# moon-rover.net
KiCad netlist of a schematic drawn in EAGLE
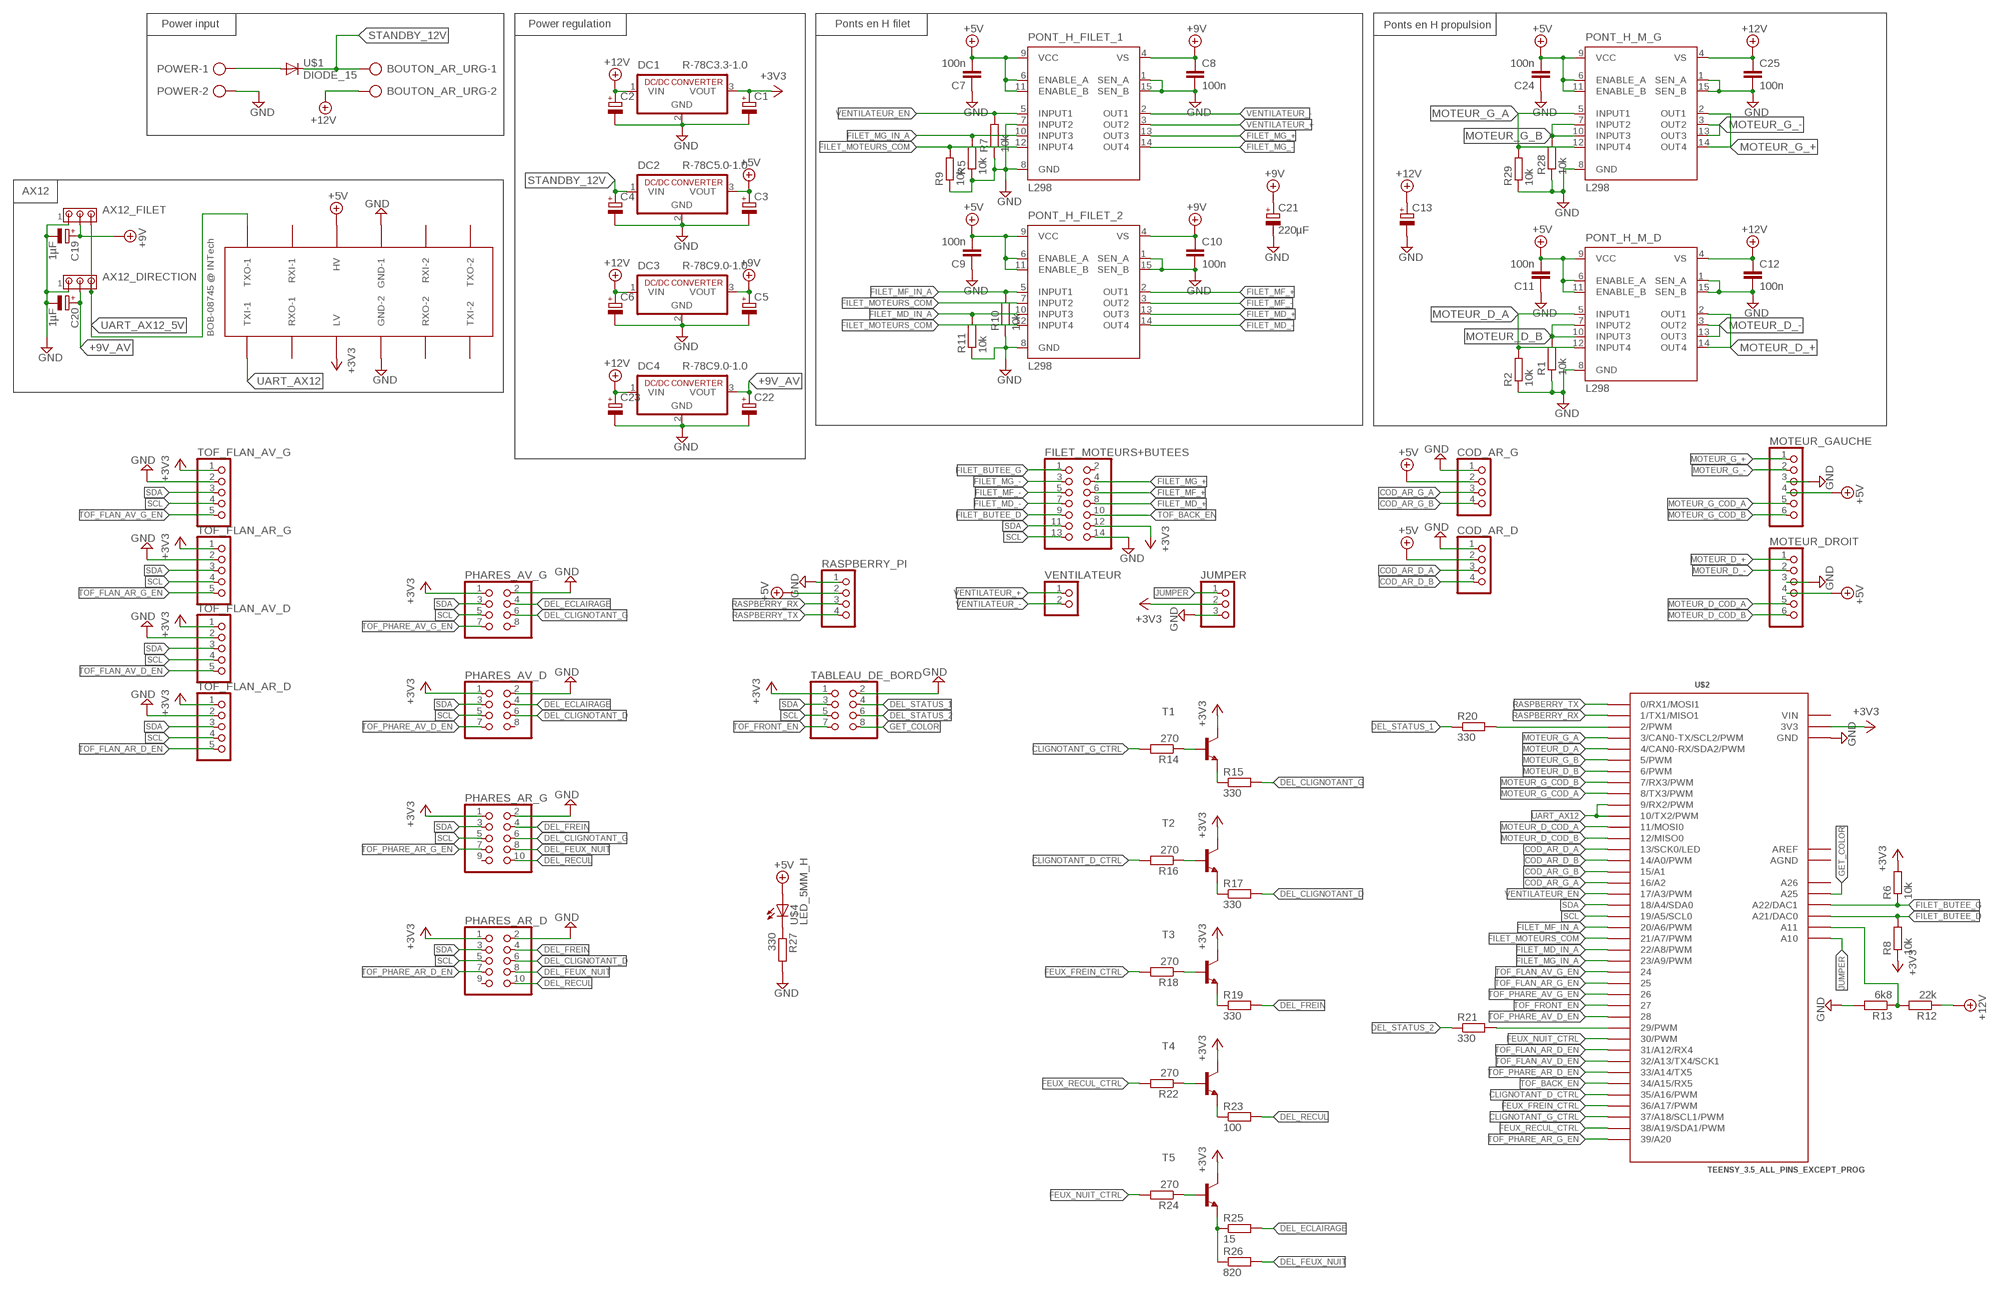
[diagram p0: schematic, sheet 1]

(export (version "E")
  (design (tool "Eeschema 10.0.6"))
  (components
    (comp (ref "AX12_DIRECTION")
      (value "MTA03-100")
      (footprint "eagle-import:10X03MTA")
      (libsource (lib "eagle-import") (part "MTA03-100"))
    )
    (comp (ref "AX12_FILET")
      (value "MTA03-100")
      (footprint "eagle-import:10X03MTA")
      (libsource (lib "eagle-import") (part "MTA03-100"))
    )
    (comp (ref "BOUTON_AR_URG")
      (value "AK300/2")
      (footprint "eagle-import:AK300_2")
      (libsource (lib "eagle-import") (part "AK300/2"))
    )
    (comp (ref "C1")
      (value "CPOL-EUE2.5-6")
      (footprint "eagle-import:E2,5-6")
      (libsource (lib "eagle-import") (part "CPOL-EUE2.5-6"))
    )
    (comp (ref "C2")
      (value "CPOL-EUE2.5-6")
      (footprint "eagle-import:E2,5-6")
      (libsource (lib "eagle-import") (part "CPOL-EUE2.5-6"))
    )
    (comp (ref "C3")
      (value "CPOL-EUE2.5-6")
      (footprint "eagle-import:E2,5-6")
      (libsource (lib "eagle-import") (part "CPOL-EUE2.5-6"))
    )
    (comp (ref "C4")
      (value "CPOL-EUE2.5-6")
      (footprint "eagle-import:E2,5-6")
      (libsource (lib "eagle-import") (part "CPOL-EUE2.5-6"))
    )
    (comp (ref "C5")
      (value "CPOL-EUE2.5-6")
      (footprint "eagle-import:E2,5-6")
      (libsource (lib "eagle-import") (part "CPOL-EUE2.5-6"))
    )
    (comp (ref "C6")
      (value "CPOL-EUE2.5-6")
      (footprint "eagle-import:E2,5-6")
      (libsource (lib "eagle-import") (part "CPOL-EUE2.5-6"))
    )
    (comp (ref "C7")
      (value "100n")
      (footprint "eagle-import:C050-024X044")
      (libsource (lib "eagle-import") (part "C-EU050-024X044"))
    )
    (comp (ref "C8")
      (value "100n")
      (footprint "eagle-import:C050-024X044")
      (libsource (lib "eagle-import") (part "C-EU050-024X044"))
    )
    (comp (ref "C9")
      (value "100n")
      (footprint "eagle-import:C050-024X044")
      (libsource (lib "eagle-import") (part "C-EU050-024X044"))
    )
    (comp (ref "C10")
      (value "100n")
      (footprint "eagle-import:C050-024X044")
      (libsource (lib "eagle-import") (part "C-EU050-024X044"))
    )
    (comp (ref "C11")
      (value "100n")
      (footprint "eagle-import:C050-024X044")
      (libsource (lib "eagle-import") (part "C-EU050-024X044"))
    )
    (comp (ref "C12")
      (value "100n")
      (footprint "eagle-import:C050-024X044")
      (libsource (lib "eagle-import") (part "C-EU050-024X044"))
    )
    (comp (ref "C13")
      (value "CPOL-EUE5-13")
      (footprint "eagle-import:E5-13")
      (libsource (lib "eagle-import") (part "resistor_CPOL-EUE5-13"))
    )
    (comp (ref "C19")
      (value "1µF")
      (footprint "eagle-import:E2,5-5")
      (libsource (lib "eagle-import") (part "CPOL-EUE2.5-5"))
    )
    (comp (ref "C20")
      (value "1µF")
      (footprint "eagle-import:E2,5-5")
      (libsource (lib "eagle-import") (part "CPOL-EUE2.5-5"))
    )
    (comp (ref "C21")
      (value "220µF")
      (footprint "eagle-import:E3,5-8")
      (libsource (lib "eagle-import") (part "CPOL-EUE3.5-8"))
    )
    (comp (ref "C22")
      (value "CPOL-EUE2.5-6")
      (footprint "eagle-import:E2,5-6")
      (libsource (lib "eagle-import") (part "CPOL-EUE2.5-6"))
    )
    (comp (ref "C23")
      (value "CPOL-EUE2.5-6")
      (footprint "eagle-import:E2,5-6")
      (libsource (lib "eagle-import") (part "CPOL-EUE2.5-6"))
    )
    (comp (ref "C24")
      (value "100n")
      (footprint "eagle-import:C050-024X044")
      (libsource (lib "eagle-import") (part "C-EU050-024X044"))
    )
    (comp (ref "C25")
      (value "100n")
      (footprint "eagle-import:C050-024X044")
      (libsource (lib "eagle-import") (part "C-EU050-024X044"))
    )
    (comp (ref "COD_AR_D")
      (value "PINHD-1X4/90")
      (footprint "eagle-import:1X04_90")
      (libsource (lib "eagle-import") (part "PINHD-1X4/90"))
    )
    (comp (ref "COD_AR_G")
      (value "PINHD-1X4/90")
      (footprint "eagle-import:1X04_90")
      (libsource (lib "eagle-import") (part "PINHD-1X4/90"))
    )
    (comp (ref "DC1")
      (value "R-78C3.3-1.0")
      (footprint "eagle-import:SIP3")
      (libsource (lib "eagle-import") (part "R-78C-1.03.3"))
    )
    (comp (ref "DC2")
      (value "R-78C5.0-1.0")
      (footprint "eagle-import:SIP3")
      (libsource (lib "eagle-import") (part "R-78C-1.05.0"))
    )
    (comp (ref "DC3")
      (value "R-78C9.0-1.0")
      (footprint "eagle-import:SIP3")
      (libsource (lib "eagle-import") (part "R-78C-1.09.0"))
    )
    (comp (ref "DC4")
      (value "R-78C9.0-1.0")
      (footprint "eagle-import:SIP3")
      (libsource (lib "eagle-import") (part "R-78C-1.09.0"))
    )
    (comp (ref "FILET_MOTEURS+BUTEES")
      (value "PINHD-2X7")
      (footprint "eagle-import:2X07")
      (libsource (lib "eagle-import") (part "PINHD-2X7"))
    )
    (comp (ref "JUMPER")
      (value "PINHD-1X3/90")
      (footprint "eagle-import:1X03_90")
      (libsource (lib "eagle-import") (part "PINHD-1X3/90"))
    )
    (comp (ref "MOTEUR_DROIT")
      (value "PINHD-1X6/90")
      (footprint "eagle-import:1X06_90")
      (libsource (lib "eagle-import") (part "PINHD-1X6/90"))
    )
    (comp (ref "MOTEUR_GAUCHE")
      (value "PINHD-1X6/90")
      (footprint "eagle-import:1X06_90")
      (libsource (lib "eagle-import") (part "PINHD-1X6/90"))
    )
    (comp (ref "PHARES_AR_D")
      (value "PINHD-2X5")
      (footprint "eagle-import:2X05")
      (libsource (lib "eagle-import") (part "PINHD-2X5"))
    )
    (comp (ref "PHARES_AR_G")
      (value "PINHD-2X5")
      (footprint "eagle-import:2X05")
      (libsource (lib "eagle-import") (part "PINHD-2X5"))
    )
    (comp (ref "PHARES_AV_D")
      (value "PINHD-2X4")
      (footprint "eagle-import:2X04")
      (libsource (lib "eagle-import") (part "PINHD-2X4"))
    )
    (comp (ref "PHARES_AV_G")
      (value "PINHD-2X4")
      (footprint "eagle-import:2X04")
      (libsource (lib "eagle-import") (part "PINHD-2X4"))
    )
    (comp (ref "PONT_H_FILET_1")
      (value "L298")
      (footprint "eagle-import:MULTIWATT-15")
      (fields (field (name "MPN") "L298N"))
      (libsource (lib "eagle-import") (part "L298"))
    )
    (comp (ref "PONT_H_FILET_2")
      (value "L298")
      (footprint "eagle-import:MULTIWATT-15")
      (fields (field (name "MPN") "L298N"))
      (libsource (lib "eagle-import") (part "L298"))
    )
    (comp (ref "PONT_H_M_D")
      (value "L298")
      (footprint "eagle-import:MULTIWATT-15")
      (fields
        (field (name "MPN") "L298N")
        (field (name "MPN_1") "L298N")
        (field (name "OC_FARNELL") "1589425")
        (field (name "OC_NEWARK") "32M1527")
      )
      (libsource (lib "eagle-import") (part "L298"))
    )
    (comp (ref "PONT_H_M_G")
      (value "L298")
      (footprint "eagle-import:MULTIWATT-15")
      (fields
        (field (name "MPN") "L298N")
        (field (name "MPN_1") "L298N")
        (field (name "OC_FARNELL") "1589425")
        (field (name "OC_NEWARK") "32M1527")
      )
      (libsource (lib "eagle-import") (part "L298"))
    )
    (comp (ref "POWER")
      (value "AK300/2")
      (footprint "eagle-import:AK300_2")
      (fields (field (name "OC_FARNELL") "unknown") (field (name "OC_NEWARK") "unknown"))
      (libsource (lib "eagle-import") (part "AK300/2"))
    )
    (comp (ref "R1")
      (value "10k")
      (footprint "eagle-import:0204_7")
      (libsource (lib "eagle-import") (part "R-EU_0204/7"))
    )
    (comp (ref "R2")
      (value "10k")
      (footprint "eagle-import:0204_7")
      (libsource (lib "eagle-import") (part "R-EU_0204/7"))
    )
    (comp (ref "R5")
      (value "10k")
      (footprint "eagle-import:0204_7")
      (libsource (lib "eagle-import") (part "R-EU_0204/7"))
    )
    (comp (ref "R6")
      (value "10k")
      (footprint "eagle-import:0204_7")
      (libsource (lib "eagle-import") (part "R-EU_0204/7"))
    )
    (comp (ref "R7")
      (value "10k")
      (footprint "eagle-import:0204_7")
      (libsource (lib "eagle-import") (part "R-EU_0204/7"))
    )
    (comp (ref "R8")
      (value "10k")
      (footprint "eagle-import:0204_7")
      (libsource (lib "eagle-import") (part "R-EU_0204/7"))
    )
    (comp (ref "R9")
      (value "10k")
      (footprint "eagle-import:0204_7")
      (libsource (lib "eagle-import") (part "R-EU_0204/7"))
    )
    (comp (ref "R10")
      (value "10k")
      (footprint "eagle-import:0204_7")
      (libsource (lib "eagle-import") (part "R-EU_0204/7"))
    )
    (comp (ref "R11")
      (value "10k")
      (footprint "eagle-import:0204_7")
      (libsource (lib "eagle-import") (part "R-EU_0204/7"))
    )
    (comp (ref "R12")
      (value "22k")
      (footprint "eagle-import:0204_7")
      (libsource (lib "eagle-import") (part "R-EU_0204/7"))
    )
    (comp (ref "R13")
      (value "6k8")
      (footprint "eagle-import:0204_7")
      (libsource (lib "eagle-import") (part "R-EU_0204/7"))
    )
    (comp (ref "R14")
      (value "270")
      (footprint "eagle-import:0204_7")
      (libsource (lib "eagle-import") (part "R-EU_0204/7"))
    )
    (comp (ref "R15")
      (value "330")
      (footprint "eagle-import:0207_2V")
      (libsource (lib "eagle-import") (part "R-EU_0207/2V"))
    )
    (comp (ref "R16")
      (value "270")
      (footprint "eagle-import:0204_7")
      (libsource (lib "eagle-import") (part "R-EU_0204/7"))
    )
    (comp (ref "R17")
      (value "330")
      (footprint "eagle-import:0207_2V")
      (libsource (lib "eagle-import") (part "R-EU_0207/2V"))
    )
    (comp (ref "R18")
      (value "270")
      (footprint "eagle-import:0204_7")
      (libsource (lib "eagle-import") (part "R-EU_0204/7"))
    )
    (comp (ref "R19")
      (value "330")
      (footprint "eagle-import:0207_2V")
      (libsource (lib "eagle-import") (part "R-EU_0207/2V"))
    )
    (comp (ref "R20")
      (value "330")
      (footprint "eagle-import:0204_7")
      (libsource (lib "eagle-import") (part "R-EU_0204/7"))
    )
    (comp (ref "R21")
      (value "330")
      (footprint "eagle-import:0207_2V")
      (libsource (lib "eagle-import") (part "R-EU_0207/2V"))
    )
    (comp (ref "R22")
      (value "270")
      (footprint "eagle-import:0204_7")
      (libsource (lib "eagle-import") (part "R-EU_0204/7"))
    )
    (comp (ref "R23")
      (value "100")
      (footprint "eagle-import:0207_2V")
      (libsource (lib "eagle-import") (part "R-EU_0207/2V"))
    )
    (comp (ref "R24")
      (value "270")
      (footprint "eagle-import:0207_2V")
      (libsource (lib "eagle-import") (part "R-EU_0207/2V"))
    )
    (comp (ref "R25")
      (value "15")
      (footprint "eagle-import:0207_2V")
      (libsource (lib "eagle-import") (part "R-EU_0207/2V"))
    )
    (comp (ref "R26")
      (value "820")
      (footprint "eagle-import:0207_2V")
      (libsource (lib "eagle-import") (part "R-EU_0207/2V"))
    )
    (comp (ref "R27")
      (value "330")
      (footprint "eagle-import:0204_7")
      (libsource (lib "eagle-import") (part "R-EU_0204/7"))
    )
    (comp (ref "R28")
      (value "10k")
      (footprint "eagle-import:0204_7")
      (libsource (lib "eagle-import") (part "R-EU_0204/7"))
    )
    (comp (ref "R29")
      (value "10k")
      (footprint "eagle-import:0204_7")
      (libsource (lib "eagle-import") (part "R-EU_0204/7"))
    )
    (comp (ref "RASPBERRY_PI")
      (value "PINHD-1X4/90")
      (footprint "eagle-import:1X04_90")
      (libsource (lib "eagle-import") (part "PINHD-1X4/90"))
    )
    (comp (ref "T1")
      (value "BC237-NPN-TO92-CBE")
      (footprint "eagle-import:TO92-CBE")
      (libsource (lib "eagle-import") (part "-NPN-TO92-CBEBC237"))
    )
    (comp (ref "T2")
      (value "BC237-NPN-TO92-CBE")
      (footprint "eagle-import:TO92-CBE")
      (libsource (lib "eagle-import") (part "-NPN-TO92-CBEBC237"))
    )
    (comp (ref "T3")
      (value "BC237-NPN-TO92-CBE")
      (footprint "eagle-import:TO92-CBE")
      (libsource (lib "eagle-import") (part "-NPN-TO92-CBEBC237"))
    )
    (comp (ref "T4")
      (value "BC237-NPN-TO92-CBE")
      (footprint "eagle-import:TO92-CBE")
      (libsource (lib "eagle-import") (part "-NPN-TO92-CBEBC237"))
    )
    (comp (ref "T5")
      (value "BC237-NPN-TO92-CBE")
      (footprint "eagle-import:TO92-CBE")
      (libsource (lib "eagle-import") (part "-NPN-TO92-CBEBC237"))
    )
    (comp (ref "TABLEAU_DE_BORD")
      (value "PINHD-2X4")
      (footprint "eagle-import:2X04")
      (libsource (lib "eagle-import") (part "PINHD-2X4"))
    )
    (comp (ref "TOF_FLAN_AR_D")
      (value "PINHD-1X5")
      (footprint "eagle-import:1X05")
      (libsource (lib "eagle-import") (part "PINHD-1X5"))
    )
    (comp (ref "TOF_FLAN_AR_G")
      (value "PINHD-1X5")
      (footprint "eagle-import:1X05")
      (libsource (lib "eagle-import") (part "PINHD-1X5"))
    )
    (comp (ref "TOF_FLAN_AV_D")
      (value "PINHD-1X5")
      (footprint "eagle-import:1X05")
      (libsource (lib "eagle-import") (part "PINHD-1X5"))
    )
    (comp (ref "TOF_FLAN_AV_G")
      (value "PINHD-1X5")
      (footprint "eagle-import:1X05")
      (libsource (lib "eagle-import") (part "PINHD-1X5"))
    )
    (comp (ref "U$1")
      (value "DIODE_15")
      (footprint "eagle-import:DO201-15")
      (libsource (lib "eagle-import") (part "DIODE_15"))
    )
    (comp (ref "U$2")
      (value "TEENSY_3.5_ALL_PINS_EXCEPT_PROG")
      (footprint "eagle-import:TEENSY_3.5_ALL_PINS_EXCEPT_PROG")
      (libsource (lib "eagle-import") (part "TEENSY_3.5_ALL_PINS_EXCEPT_PROG"))
    )
    (comp (ref "U$3")
      (value "BOB-08745")
      (footprint "eagle-import:BOB-08745")
      (libsource (lib "eagle-import") (part "BOB-08745"))
    )
    (comp (ref "U$4")
      (value "LED_5MM_H")
      (footprint "eagle-import:Q62902-B155")
      (libsource (lib "eagle-import") (part "LED_5MM_H"))
    )
    (comp (ref "VENTILATEUR")
      (value "PINHD-1X2/90")
      (footprint "eagle-import:1X02_90")
      (libsource (lib "eagle-import") (part "PINHD-1X2/90"))
    )
  )
  (nets
    (net (code "1") (name "+3V3") (class "Default")
      (node (ref "C1") (pin "+") (pinfunction "+_+") (pintype "passive"))
      (node (ref "DC1") (pin "3") (pinfunction "VOUT_3") (pintype "passive"))
      (node (ref "FILET_MOTEURS+BUTEES") (pin "12") (pinfunction "12_12") (pintype "passive"))
      (node (ref "JUMPER") (pin "2") (pinfunction "2_2") (pintype "passive"))
      (node (ref "PHARES_AR_D") (pin "1") (pinfunction "1_1") (pintype "passive"))
      (node (ref "PHARES_AR_G") (pin "1") (pinfunction "1_1") (pintype "passive"))
      (node (ref "PHARES_AV_D") (pin "1") (pinfunction "1_1") (pintype "passive"))
      (node (ref "PHARES_AV_G") (pin "1") (pinfunction "1_1") (pintype "passive"))
      (node (ref "R6") (pin "2") (pinfunction "2_2") (pintype "passive"))
      (node (ref "R8") (pin "1") (pinfunction "1_1") (pintype "passive"))
      (node (ref "T1") (pin "C") (pinfunction "C_C") (pintype "passive"))
      (node (ref "T2") (pin "C") (pinfunction "C_C") (pintype "passive"))
      (node (ref "T3") (pin "C") (pinfunction "C_C") (pintype "passive"))
      (node (ref "T4") (pin "C") (pinfunction "C_C") (pintype "passive"))
      (node (ref "T5") (pin "C") (pinfunction "C_C") (pintype "passive"))
      (node (ref "TABLEAU_DE_BORD") (pin "1") (pinfunction "1_1") (pintype "passive"))
      (node (ref "TOF_FLAN_AR_D") (pin "1") (pinfunction "1_1") (pintype "passive"))
      (node (ref "TOF_FLAN_AR_G") (pin "1") (pinfunction "1_1") (pintype "passive"))
      (node (ref "TOF_FLAN_AV_D") (pin "1") (pinfunction "1_1") (pintype "passive"))
      (node (ref "TOF_FLAN_AV_G") (pin "1") (pinfunction "1_1") (pintype "passive"))
      (node (ref "U$2") (pin "3.3V") (pinfunction "3V3_3.3V") (pintype "power_in"))
      (node (ref "U$2") (pin "3.3V3") (pinfunction "3V3_3.3V3") (pintype "power_in"))
      (node (ref "U$3") (pin "LV") (pinfunction "LV_LV") (pintype "bidirectional"))
    )
    (net (code "2") (name "+5V") (class "Default")
      (node (ref "C11") (pin "2") (pinfunction "2_2") (pintype "passive"))
      (node (ref "C24") (pin "2") (pinfunction "2_2") (pintype "passive"))
      (node (ref "C3") (pin "+") (pinfunction "+_+") (pintype "passive"))
      (node (ref "C7") (pin "2") (pinfunction "2_2") (pintype "passive"))
      (node (ref "C9") (pin "2") (pinfunction "2_2") (pintype "passive"))
      (node (ref "COD_AR_D") (pin "2") (pinfunction "2_2") (pintype "passive"))
      (node (ref "COD_AR_G") (pin "2") (pinfunction "2_2") (pintype "passive"))
      (node (ref "DC2") (pin "3") (pinfunction "VOUT_3") (pintype "passive"))
      (node (ref "MOTEUR_DROIT") (pin "4") (pinfunction "4_4") (pintype "passive"))
      (node (ref "MOTEUR_GAUCHE") (pin "4") (pinfunction "4_4") (pintype "passive"))
      (node (ref "PONT_H_FILET_1") (pin "11") (pinfunction "ENABLE_B_11") (pintype "input"))
      (node (ref "PONT_H_FILET_1") (pin "6") (pinfunction "ENABLE_A_6") (pintype "input"))
      (node (ref "PONT_H_FILET_1") (pin "9") (pinfunction "VCC_9") (pintype "power_in"))
      (node (ref "PONT_H_FILET_2") (pin "11") (pinfunction "ENABLE_B_11") (pintype "input"))
      (node (ref "PONT_H_FILET_2") (pin "6") (pinfunction "ENABLE_A_6") (pintype "input"))
      (node (ref "PONT_H_FILET_2") (pin "9") (pinfunction "VCC_9") (pintype "power_in"))
      (node (ref "PONT_H_M_D") (pin "11") (pinfunction "ENABLE_B_11") (pintype "input"))
      (node (ref "PONT_H_M_D") (pin "6") (pinfunction "ENABLE_A_6") (pintype "input"))
      (node (ref "PONT_H_M_D") (pin "9") (pinfunction "VCC_9") (pintype "power_in"))
      (node (ref "PONT_H_M_G") (pin "11") (pinfunction "ENABLE_B_11") (pintype "input"))
      (node (ref "PONT_H_M_G") (pin "6") (pinfunction "ENABLE_A_6") (pintype "input"))
      (node (ref "PONT_H_M_G") (pin "9") (pinfunction "VCC_9") (pintype "power_in"))
      (node (ref "RASPBERRY_PI") (pin "2") (pinfunction "2_2") (pintype "passive"))
      (node (ref "U$3") (pin "HV") (pinfunction "HV_HV") (pintype "bidirectional"))
      (node (ref "U$4") (pin "A+") (pinfunction "A+_A+") (pintype "passive"))
    )
    (net (code "3") (name "+9V") (class "Default")
      (node (ref "AX12_FILET") (pin "2") (pinfunction "2_2") (pintype "passive"))
      (node (ref "C10") (pin "1") (pinfunction "1_1") (pintype "passive"))
      (node (ref "C19") (pin "+") (pinfunction "+_+") (pintype "passive"))
      (node (ref "C21") (pin "+") (pinfunction "+_+") (pintype "passive"))
      (node (ref "C5") (pin "+") (pinfunction "+_+") (pintype "passive"))
      (node (ref "C8") (pin "1") (pinfunction "1_1") (pintype "passive"))
      (node (ref "DC3") (pin "3") (pinfunction "VOUT_3") (pintype "passive"))
      (node (ref "PONT_H_FILET_1") (pin "4") (pinfunction "VS_4") (pintype "power_in"))
      (node (ref "PONT_H_FILET_2") (pin "4") (pinfunction "VS_4") (pintype "power_in"))
    )
    (net (code "4") (name "+9V_AV") (class "Default")
      (node (ref "AX12_DIRECTION") (pin "2") (pinfunction "2_2") (pintype "passive"))
      (node (ref "C20") (pin "+") (pinfunction "+_+") (pintype "passive"))
      (node (ref "C22") (pin "+") (pinfunction "+_+") (pintype "passive"))
      (node (ref "DC4") (pin "3") (pinfunction "VOUT_3") (pintype "passive"))
    )
    (net (code "5") (name "+12V") (class "Default")
      (node (ref "BOUTON_AR_URG") (pin "2") (pinfunction "KL_2") (pintype "passive"))
      (node (ref "C12") (pin "1") (pinfunction "1_1") (pintype "passive"))
      (node (ref "C13") (pin "+") (pinfunction "+_+") (pintype "passive"))
      (node (ref "C2") (pin "+") (pinfunction "+_+") (pintype "passive"))
      (node (ref "C23") (pin "+") (pinfunction "+_+") (pintype "passive"))
      (node (ref "C25") (pin "1") (pinfunction "1_1") (pintype "passive"))
      (node (ref "C6") (pin "+") (pinfunction "+_+") (pintype "passive"))
      (node (ref "DC1") (pin "1") (pinfunction "VIN_1") (pintype "passive"))
      (node (ref "DC3") (pin "1") (pinfunction "VIN_1") (pintype "passive"))
      (node (ref "DC4") (pin "1") (pinfunction "VIN_1") (pintype "passive"))
      (node (ref "PONT_H_M_D") (pin "4") (pinfunction "VS_4") (pintype "power_in"))
      (node (ref "PONT_H_M_G") (pin "4") (pinfunction "VS_4") (pintype "power_in"))
      (node (ref "R12") (pin "1") (pinfunction "1_1") (pintype "passive"))
    )
    (net (code "6") (name "/AGND") (class "Default")
      (node (ref "U$2") (pin "AGND") (pinfunction "AGND_AGND") (pintype "power_in"))
    )
    (net (code "7") (name "/AREF") (class "Default")
      (node (ref "U$2") (pin "AREF") (pinfunction "AREF_AREF") (pintype "power_in"))
    )
    (net (code "8") (name "/VIN") (class "Default")
      (node (ref "U$2") (pin "VIN") (pinfunction "VIN_VIN") (pintype "power_in"))
    )
    (net (code "9") (name "CLIGNOTANT_D_CTRL") (class "Default")
      (node (ref "R16") (pin "2") (pinfunction "2_2") (pintype "passive"))
      (node (ref "U$2") (pin "35/A16") (pinfunction "35/A16/PWM_35/A16") (pintype "bidirectional"))
    )
    (net (code "10") (name "CLIGNOTANT_G_CTRL") (class "Default")
      (node (ref "R14") (pin "2") (pinfunction "2_2") (pintype "passive"))
      (node (ref "U$2") (pin "37/A18") (pinfunction "37/A18/SCL1/PWM_37/A18") (pintype "bidirectional"))
    )
    (net (code "11") (name "COD_AR_D_A") (class "Default")
      (node (ref "COD_AR_D") (pin "3") (pinfunction "3_3") (pintype "passive"))
      (node (ref "U$2") (pin "13") (pinfunction "13/SCK0/LED_13") (pintype "bidirectional"))
    )
    (net (code "12") (name "COD_AR_D_B") (class "Default")
      (node (ref "COD_AR_D") (pin "4") (pinfunction "4_4") (pintype "passive"))
      (node (ref "U$2") (pin "14/A0") (pinfunction "14/A0/PWM_14/A0") (pintype "bidirectional"))
    )
    (net (code "13") (name "COD_AR_G_A") (class "Default")
      (node (ref "COD_AR_G") (pin "3") (pinfunction "3_3") (pintype "passive"))
      (node (ref "U$2") (pin "16/A2") (pinfunction "16/A2_16/A2") (pintype "bidirectional"))
    )
    (net (code "14") (name "COD_AR_G_B") (class "Default")
      (node (ref "COD_AR_G") (pin "4") (pinfunction "4_4") (pintype "passive"))
      (node (ref "U$2") (pin "15/A1") (pinfunction "15/A1_15/A1") (pintype "bidirectional"))
    )
    (net (code "15") (name "DEL_CLIGNOTANT_D") (class "Default")
      (node (ref "PHARES_AR_D") (pin "6") (pinfunction "6_6") (pintype "passive"))
      (node (ref "PHARES_AV_D") (pin "6") (pinfunction "6_6") (pintype "passive"))
      (node (ref "R17") (pin "2") (pinfunction "2_2") (pintype "passive"))
    )
    (net (code "16") (name "DEL_CLIGNOTANT_G") (class "Default")
      (node (ref "PHARES_AR_G") (pin "6") (pinfunction "6_6") (pintype "passive"))
      (node (ref "PHARES_AV_G") (pin "6") (pinfunction "6_6") (pintype "passive"))
      (node (ref "R15") (pin "2") (pinfunction "2_2") (pintype "passive"))
    )
    (net (code "17") (name "DEL_ECLAIRAGE") (class "Default")
      (node (ref "PHARES_AV_D") (pin "4") (pinfunction "4_4") (pintype "passive"))
      (node (ref "PHARES_AV_G") (pin "4") (pinfunction "4_4") (pintype "passive"))
      (node (ref "R25") (pin "2") (pinfunction "2_2") (pintype "passive"))
    )
    (net (code "18") (name "DEL_FEUX_NUIT") (class "Default")
      (node (ref "PHARES_AR_D") (pin "8") (pinfunction "8_8") (pintype "passive"))
      (node (ref "PHARES_AR_G") (pin "8") (pinfunction "8_8") (pintype "passive"))
      (node (ref "R26") (pin "2") (pinfunction "2_2") (pintype "passive"))
    )
    (net (code "19") (name "DEL_FREIN") (class "Default")
      (node (ref "PHARES_AR_D") (pin "4") (pinfunction "4_4") (pintype "passive"))
      (node (ref "PHARES_AR_G") (pin "4") (pinfunction "4_4") (pintype "passive"))
      (node (ref "R19") (pin "2") (pinfunction "2_2") (pintype "passive"))
    )
    (net (code "20") (name "DEL_RECUL") (class "Default")
      (node (ref "PHARES_AR_D") (pin "10") (pinfunction "10_10") (pintype "passive"))
      (node (ref "PHARES_AR_G") (pin "10") (pinfunction "10_10") (pintype "passive"))
      (node (ref "R23") (pin "2") (pinfunction "2_2") (pintype "passive"))
    )
    (net (code "21") (name "DEL_STATUS_1") (class "Default")
      (node (ref "R20") (pin "1") (pinfunction "1_1") (pintype "passive"))
      (node (ref "TABLEAU_DE_BORD") (pin "4") (pinfunction "4_4") (pintype "passive"))
    )
    (net (code "22") (name "DEL_STATUS_2") (class "Default")
      (node (ref "R21") (pin "1") (pinfunction "1_1") (pintype "passive"))
      (node (ref "TABLEAU_DE_BORD") (pin "6") (pinfunction "6_6") (pintype "passive"))
    )
    (net (code "23") (name "FEUX_FREIN_CTRL") (class "Default")
      (node (ref "R18") (pin "2") (pinfunction "2_2") (pintype "passive"))
      (node (ref "U$2") (pin "36/A17") (pinfunction "36/A17/PWM_36/A17") (pintype "bidirectional"))
    )
    (net (code "24") (name "FEUX_NUIT_CTRL") (class "Default")
      (node (ref "R24") (pin "2") (pinfunction "2_2") (pintype "passive"))
      (node (ref "U$2") (pin "30") (pinfunction "30/PWM_30") (pintype "bidirectional"))
    )
    (net (code "25") (name "FEUX_RECUL_CTRL") (class "Default")
      (node (ref "R22") (pin "2") (pinfunction "2_2") (pintype "passive"))
      (node (ref "U$2") (pin "38/A19") (pinfunction "38/A19/SDA1/PWM_38/A19") (pintype "bidirectional"))
    )
    (net (code "26") (name "FILET_BUTEE_D") (class "Default")
      (node (ref "FILET_MOTEURS+BUTEES") (pin "9") (pinfunction "9_9") (pintype "passive"))
      (node (ref "R8") (pin "2") (pinfunction "2_2") (pintype "passive"))
      (node (ref "U$2") (pin "A21") (pinfunction "A21/DAC0_A21") (pintype "bidirectional"))
    )
    (net (code "27") (name "FILET_BUTEE_G") (class "Default")
      (node (ref "FILET_MOTEURS+BUTEES") (pin "1") (pinfunction "1_1") (pintype "passive"))
      (node (ref "R6") (pin "1") (pinfunction "1_1") (pintype "passive"))
      (node (ref "U$2") (pin "A22") (pinfunction "A22/DAC1_A22") (pintype "bidirectional"))
    )
    (net (code "28") (name "FILET_MD_+") (class "Default")
      (node (ref "FILET_MOTEURS+BUTEES") (pin "8") (pinfunction "8_8") (pintype "passive"))
      (node (ref "PONT_H_FILET_2") (pin "13") (pinfunction "OUT3_13") (pintype "output"))
    )
    (net (code "29") (name "FILET_MD_-") (class "Default")
      (node (ref "FILET_MOTEURS+BUTEES") (pin "7") (pinfunction "7_7") (pintype "passive"))
      (node (ref "PONT_H_FILET_2") (pin "14") (pinfunction "OUT4_14") (pintype "output"))
    )
    (net (code "30") (name "FILET_MD_IN_A") (class "Default")
      (node (ref "PONT_H_FILET_2") (pin "10") (pinfunction "INPUT3_10") (pintype "input"))
      (node (ref "R11") (pin "2") (pinfunction "2_2") (pintype "passive"))
      (node (ref "U$2") (pin "22/A8") (pinfunction "22/A8/PWM_22/A8") (pintype "bidirectional"))
    )
    (net (code "31") (name "FILET_MF_+") (class "Default")
      (node (ref "FILET_MOTEURS+BUTEES") (pin "6") (pinfunction "6_6") (pintype "passive"))
      (node (ref "PONT_H_FILET_2") (pin "2") (pinfunction "OUT1_2") (pintype "output"))
    )
    (net (code "32") (name "FILET_MF_-") (class "Default")
      (node (ref "FILET_MOTEURS+BUTEES") (pin "5") (pinfunction "5_5") (pintype "passive"))
      (node (ref "PONT_H_FILET_2") (pin "3") (pinfunction "OUT2_3") (pintype "output"))
    )
    (net (code "33") (name "FILET_MF_IN_A") (class "Default")
      (node (ref "PONT_H_FILET_2") (pin "5") (pinfunction "INPUT1_5") (pintype "input"))
      (node (ref "R10") (pin "2") (pinfunction "2_2") (pintype "passive"))
      (node (ref "U$2") (pin "20/A6") (pinfunction "20/A6/PWM_20/A6") (pintype "bidirectional"))
    )
    (net (code "34") (name "FILET_MG_+") (class "Default")
      (node (ref "FILET_MOTEURS+BUTEES") (pin "4") (pinfunction "4_4") (pintype "passive"))
      (node (ref "PONT_H_FILET_1") (pin "13") (pinfunction "OUT3_13") (pintype "output"))
    )
    (net (code "35") (name "FILET_MG_-") (class "Default")
      (node (ref "FILET_MOTEURS+BUTEES") (pin "3") (pinfunction "3_3") (pintype "passive"))
      (node (ref "PONT_H_FILET_1") (pin "14") (pinfunction "OUT4_14") (pintype "output"))
    )
    (net (code "36") (name "FILET_MG_IN_A") (class "Default")
      (node (ref "PONT_H_FILET_1") (pin "10") (pinfunction "INPUT3_10") (pintype "input"))
      (node (ref "R5") (pin "2") (pinfunction "2_2") (pintype "passive"))
      (node (ref "U$2") (pin "23/A9") (pinfunction "23/A9/PWM_23/A9") (pintype "bidirectional"))
    )
    (net (code "37") (name "FILET_MOTEURS_COM") (class "Default")
      (node (ref "PONT_H_FILET_1") (pin "12") (pinfunction "INPUT4_12") (pintype "input"))
      (node (ref "PONT_H_FILET_2") (pin "12") (pinfunction "INPUT4_12") (pintype "input"))
      (node (ref "PONT_H_FILET_2") (pin "7") (pinfunction "INPUT2_7") (pintype "input"))
      (node (ref "R9") (pin "2") (pinfunction "2_2") (pintype "passive"))
      (node (ref "U$2") (pin "21/A7") (pinfunction "21/A7/PWM_21/A7") (pintype "bidirectional"))
    )
    (net (code "38") (name "GET_COLOR") (class "Default")
      (node (ref "TABLEAU_DE_BORD") (pin "8") (pinfunction "8_8") (pintype "passive"))
      (node (ref "U$2") (pin "A25") (pinfunction "A25_A25") (pintype "bidirectional"))
    )
    (net (code "39") (name "GND") (class "Default")
      (node (ref "AX12_DIRECTION") (pin "1") (pinfunction "1_1") (pintype "passive"))
      (node (ref "AX12_FILET") (pin "1") (pinfunction "1_1") (pintype "passive"))
      (node (ref "C1") (pin "-") (pinfunction "-_-") (pintype "passive"))
      (node (ref "C10") (pin "2") (pinfunction "2_2") (pintype "passive"))
      (node (ref "C11") (pin "1") (pinfunction "1_1") (pintype "passive"))
      (node (ref "C12") (pin "2") (pinfunction "2_2") (pintype "passive"))
      (node (ref "C13") (pin "-") (pinfunction "-_-") (pintype "passive"))
      (node (ref "C19") (pin "-") (pinfunction "-_-") (pintype "passive"))
      (node (ref "C2") (pin "-") (pinfunction "-_-") (pintype "passive"))
      (node (ref "C20") (pin "-") (pinfunction "-_-") (pintype "passive"))
      (node (ref "C21") (pin "-") (pinfunction "-_-") (pintype "passive"))
      (node (ref "C22") (pin "-") (pinfunction "-_-") (pintype "passive"))
      (node (ref "C23") (pin "-") (pinfunction "-_-") (pintype "passive"))
      (node (ref "C24") (pin "1") (pinfunction "1_1") (pintype "passive"))
      (node (ref "C25") (pin "2") (pinfunction "2_2") (pintype "passive"))
      (node (ref "C3") (pin "-") (pinfunction "-_-") (pintype "passive"))
      (node (ref "C4") (pin "-") (pinfunction "-_-") (pintype "passive"))
      (node (ref "C5") (pin "-") (pinfunction "-_-") (pintype "passive"))
      (node (ref "C6") (pin "-") (pinfunction "-_-") (pintype "passive"))
      (node (ref "C7") (pin "1") (pinfunction "1_1") (pintype "passive"))
      (node (ref "C8") (pin "2") (pinfunction "2_2") (pintype "passive"))
      (node (ref "C9") (pin "1") (pinfunction "1_1") (pintype "passive"))
      (node (ref "COD_AR_D") (pin "1") (pinfunction "1_1") (pintype "passive"))
      (node (ref "COD_AR_G") (pin "1") (pinfunction "1_1") (pintype "passive"))
      (node (ref "DC1") (pin "2") (pinfunction "GND_2") (pintype "passive"))
      (node (ref "DC2") (pin "2") (pinfunction "GND_2") (pintype "passive"))
      (node (ref "DC3") (pin "2") (pinfunction "GND_2") (pintype "passive"))
      (node (ref "DC4") (pin "2") (pinfunction "GND_2") (pintype "passive"))
      (node (ref "FILET_MOTEURS+BUTEES") (pin "14") (pinfunction "14_14") (pintype "passive"))
      (node (ref "JUMPER") (pin "3") (pinfunction "3_3") (pintype "passive"))
      (node (ref "MOTEUR_DROIT") (pin "3") (pinfunction "3_3") (pintype "passive"))
      (node (ref "MOTEUR_GAUCHE") (pin "3") (pinfunction "3_3") (pintype "passive"))
      (node (ref "PHARES_AR_D") (pin "2") (pinfunction "2_2") (pintype "passive"))
      (node (ref "PHARES_AR_G") (pin "2") (pinfunction "2_2") (pintype "passive"))
      (node (ref "PHARES_AV_D") (pin "2") (pinfunction "2_2") (pintype "passive"))
      (node (ref "PHARES_AV_G") (pin "2") (pinfunction "2_2") (pintype "passive"))
      (node (ref "PONT_H_FILET_1") (pin "1") (pinfunction "SEN_A_1") (pintype "input"))
      (node (ref "PONT_H_FILET_1") (pin "15") (pinfunction "SEN_B_15") (pintype "input"))
      (node (ref "PONT_H_FILET_1") (pin "7") (pinfunction "INPUT2_7") (pintype "input"))
      (node (ref "PONT_H_FILET_1") (pin "8") (pinfunction "GND_8") (pintype "power_in"))
      (node (ref "PONT_H_FILET_2") (pin "1") (pinfunction "SEN_A_1") (pintype "input"))
      (node (ref "PONT_H_FILET_2") (pin "15") (pinfunction "SEN_B_15") (pintype "input"))
      (node (ref "PONT_H_FILET_2") (pin "8") (pinfunction "GND_8") (pintype "power_in"))
      (node (ref "PONT_H_M_D") (pin "1") (pinfunction "SEN_A_1") (pintype "input"))
      (node (ref "PONT_H_M_D") (pin "15") (pinfunction "SEN_B_15") (pintype "input"))
      (node (ref "PONT_H_M_D") (pin "8") (pinfunction "GND_8") (pintype "power_in"))
      (node (ref "PONT_H_M_G") (pin "1") (pinfunction "SEN_A_1") (pintype "input"))
      (node (ref "PONT_H_M_G") (pin "15") (pinfunction "SEN_B_15") (pintype "input"))
      (node (ref "PONT_H_M_G") (pin "8") (pinfunction "GND_8") (pintype "power_in"))
      (node (ref "POWER") (pin "2") (pinfunction "KL_2") (pintype "passive"))
      (node (ref "R1") (pin "1") (pinfunction "1_1") (pintype "passive"))
      (node (ref "R10") (pin "1") (pinfunction "1_1") (pintype "passive"))
      (node (ref "R11") (pin "1") (pinfunction "1_1") (pintype "passive"))
      (node (ref "R13") (pin "2") (pinfunction "2_2") (pintype "passive"))
      (node (ref "R2") (pin "1") (pinfunction "1_1") (pintype "passive"))
      (node (ref "R27") (pin "2") (pinfunction "2_2") (pintype "passive"))
      (node (ref "R28") (pin "1") (pinfunction "1_1") (pintype "passive"))
      (node (ref "R29") (pin "1") (pinfunction "1_1") (pintype "passive"))
      (node (ref "R5") (pin "1") (pinfunction "1_1") (pintype "passive"))
      (node (ref "R7") (pin "1") (pinfunction "1_1") (pintype "passive"))
      (node (ref "R9") (pin "1") (pinfunction "1_1") (pintype "passive"))
      (node (ref "RASPBERRY_PI") (pin "1") (pinfunction "1_1") (pintype "passive"))
      (node (ref "TABLEAU_DE_BORD") (pin "2") (pinfunction "2_2") (pintype "passive"))
      (node (ref "TOF_FLAN_AR_D") (pin "2") (pinfunction "2_2") (pintype "passive"))
      (node (ref "TOF_FLAN_AR_G") (pin "2") (pinfunction "2_2") (pintype "passive"))
      (node (ref "TOF_FLAN_AV_D") (pin "2") (pinfunction "2_2") (pintype "passive"))
      (node (ref "TOF_FLAN_AV_G") (pin "2") (pinfunction "2_2") (pintype "passive"))
      (node (ref "U$2") (pin "GND") (pinfunction "GND_GND") (pintype "power_in"))
      (node (ref "U$2") (pin "GND1") (pinfunction "GND_GND1") (pintype "power_in"))
      (node (ref "U$2") (pin "GND3") (pinfunction "GND_GND3") (pintype "power_in"))
      (node (ref "U$2") (pin "GND4") (pinfunction "GND_GND4") (pintype "power_in"))
      (node (ref "U$3") (pin "GND-1") (pinfunction "GND-1_GND-1") (pintype "bidirectional"))
      (node (ref "U$3") (pin "GND-2") (pinfunction "GND-2_GND-2") (pintype "bidirectional"))
    )
    (net (code "40") (name "JUMPER") (class "Default")
      (node (ref "JUMPER") (pin "1") (pinfunction "1_1") (pintype "passive"))
      (node (ref "U$2") (pin "A10") (pinfunction "A10_A10") (pintype "bidirectional"))
    )
    (net (code "41") (name "MOTEUR_D_+") (class "Default")
      (node (ref "MOTEUR_DROIT") (pin "1") (pinfunction "1_1") (pintype "passive"))
      (node (ref "PONT_H_M_D") (pin "14") (pinfunction "OUT4_14") (pintype "output"))
      (node (ref "PONT_H_M_D") (pin "2") (pinfunction "OUT1_2") (pintype "output"))
    )
    (net (code "42") (name "MOTEUR_D_-") (class "Default")
      (node (ref "MOTEUR_DROIT") (pin "2") (pinfunction "2_2") (pintype "passive"))
      (node (ref "PONT_H_M_D") (pin "13") (pinfunction "OUT3_13") (pintype "output"))
      (node (ref "PONT_H_M_D") (pin "3") (pinfunction "OUT2_3") (pintype "output"))
    )
    (net (code "43") (name "MOTEUR_D_A") (class "Default")
      (node (ref "PONT_H_M_D") (pin "12") (pinfunction "INPUT4_12") (pintype "input"))
      (node (ref "PONT_H_M_D") (pin "5") (pinfunction "INPUT1_5") (pintype "input"))
      (node (ref "R2") (pin "2") (pinfunction "2_2") (pintype "passive"))
      (node (ref "U$2") (pin "4") (pinfunction "4/CAN0-RX/SDA2/PWM_4") (pintype "bidirectional"))
    )
    (net (code "44") (name "MOTEUR_D_B") (class "Default")
      (node (ref "PONT_H_M_D") (pin "10") (pinfunction "INPUT3_10") (pintype "input"))
      (node (ref "PONT_H_M_D") (pin "7") (pinfunction "INPUT2_7") (pintype "input"))
      (node (ref "R1") (pin "2") (pinfunction "2_2") (pintype "passive"))
      (node (ref "U$2") (pin "6") (pinfunction "6/PWM_6") (pintype "bidirectional"))
    )
    (net (code "45") (name "MOTEUR_D_COD_A") (class "Default")
      (node (ref "MOTEUR_DROIT") (pin "5") (pinfunction "5_5") (pintype "passive"))
      (node (ref "U$2") (pin "11") (pinfunction "11/MOSI0_11") (pintype "bidirectional"))
    )
    (net (code "46") (name "MOTEUR_D_COD_B") (class "Default")
      (node (ref "MOTEUR_DROIT") (pin "6") (pinfunction "6_6") (pintype "passive"))
      (node (ref "U$2") (pin "12") (pinfunction "12/MISO0_12") (pintype "bidirectional"))
    )
    (net (code "47") (name "MOTEUR_G_+") (class "Default")
      (node (ref "MOTEUR_GAUCHE") (pin "1") (pinfunction "1_1") (pintype "passive"))
      (node (ref "PONT_H_M_G") (pin "14") (pinfunction "OUT4_14") (pintype "output"))
      (node (ref "PONT_H_M_G") (pin "2") (pinfunction "OUT1_2") (pintype "output"))
    )
    (net (code "48") (name "MOTEUR_G_-") (class "Default")
      (node (ref "MOTEUR_GAUCHE") (pin "2") (pinfunction "2_2") (pintype "passive"))
      (node (ref "PONT_H_M_G") (pin "13") (pinfunction "OUT3_13") (pintype "output"))
      (node (ref "PONT_H_M_G") (pin "3") (pinfunction "OUT2_3") (pintype "output"))
    )
    (net (code "49") (name "MOTEUR_G_A") (class "Default")
      (node (ref "PONT_H_M_G") (pin "12") (pinfunction "INPUT4_12") (pintype "input"))
      (node (ref "PONT_H_M_G") (pin "5") (pinfunction "INPUT1_5") (pintype "input"))
      (node (ref "R29") (pin "2") (pinfunction "2_2") (pintype "passive"))
      (node (ref "U$2") (pin "3") (pinfunction "3/CAN0-TX/SCL2/PWM_3") (pintype "bidirectional"))
    )
    (net (code "50") (name "MOTEUR_G_B") (class "Default")
      (node (ref "PONT_H_M_G") (pin "10") (pinfunction "INPUT3_10") (pintype "input"))
      (node (ref "PONT_H_M_G") (pin "7") (pinfunction "INPUT2_7") (pintype "input"))
      (node (ref "R28") (pin "2") (pinfunction "2_2") (pintype "passive"))
      (node (ref "U$2") (pin "5") (pinfunction "5/PWM_5") (pintype "bidirectional"))
    )
    (net (code "51") (name "MOTEUR_G_COD_A") (class "Default")
      (node (ref "MOTEUR_GAUCHE") (pin "5") (pinfunction "5_5") (pintype "passive"))
      (node (ref "U$2") (pin "8") (pinfunction "8/TX3/PWM_8") (pintype "bidirectional"))
    )
    (net (code "52") (name "MOTEUR_G_COD_B") (class "Default")
      (node (ref "MOTEUR_GAUCHE") (pin "6") (pinfunction "6_6") (pintype "passive"))
      (node (ref "U$2") (pin "7") (pinfunction "7/RX3/PWM_7") (pintype "bidirectional"))
    )
    (net (code "53") (name "Net-(POWERA-KL)") (class "Default")
      (node (ref "POWER") (pin "1") (pinfunction "KL_1") (pintype "passive"))
      (node (ref "U$1") (pin "A") (pinfunction "A+_A") (pintype "passive"))
    )
    (net (code "54") (name "Net-(R12-Pad2)") (class "Default")
      (node (ref "R12") (pin "2") (pinfunction "2_2") (pintype "passive"))
      (node (ref "R13") (pin "1") (pinfunction "1_1") (pintype "passive"))
      (node (ref "U$2") (pin "A11") (pinfunction "A11_A11") (pintype "bidirectional"))
    )
    (net (code "55") (name "Net-(R14-Pad1)") (class "Default")
      (node (ref "R14") (pin "1") (pinfunction "1_1") (pintype "passive"))
      (node (ref "T1") (pin "B") (pinfunction "B_B") (pintype "passive"))
    )
    (net (code "56") (name "Net-(R15-Pad1)") (class "Default")
      (node (ref "R15") (pin "1") (pinfunction "1_1") (pintype "passive"))
      (node (ref "T1") (pin "E") (pinfunction "E_E") (pintype "passive"))
    )
    (net (code "57") (name "Net-(R16-Pad1)") (class "Default")
      (node (ref "R16") (pin "1") (pinfunction "1_1") (pintype "passive"))
      (node (ref "T2") (pin "B") (pinfunction "B_B") (pintype "passive"))
    )
    (net (code "58") (name "Net-(R17-Pad1)") (class "Default")
      (node (ref "R17") (pin "1") (pinfunction "1_1") (pintype "passive"))
      (node (ref "T2") (pin "E") (pinfunction "E_E") (pintype "passive"))
    )
    (net (code "59") (name "Net-(R18-Pad1)") (class "Default")
      (node (ref "R18") (pin "1") (pinfunction "1_1") (pintype "passive"))
      (node (ref "T3") (pin "B") (pinfunction "B_B") (pintype "passive"))
    )
    (net (code "60") (name "Net-(R19-Pad1)") (class "Default")
      (node (ref "R19") (pin "1") (pinfunction "1_1") (pintype "passive"))
      (node (ref "T3") (pin "E") (pinfunction "E_E") (pintype "passive"))
    )
    (net (code "61") (name "Net-(R22-Pad1)") (class "Default")
      (node (ref "R22") (pin "1") (pinfunction "1_1") (pintype "passive"))
      (node (ref "T4") (pin "B") (pinfunction "B_B") (pintype "passive"))
    )
    (net (code "62") (name "Net-(R23-Pad1)") (class "Default")
      (node (ref "R23") (pin "1") (pinfunction "1_1") (pintype "passive"))
      (node (ref "T4") (pin "E") (pinfunction "E_E") (pintype "passive"))
    )
    (net (code "63") (name "Net-(R24-Pad1)") (class "Default")
      (node (ref "R24") (pin "1") (pinfunction "1_1") (pintype "passive"))
      (node (ref "T5") (pin "B") (pinfunction "B_B") (pintype "passive"))
    )
    (net (code "64") (name "Net-(R25-Pad1)") (class "Default")
      (node (ref "R25") (pin "1") (pinfunction "1_1") (pintype "passive"))
      (node (ref "R26") (pin "1") (pinfunction "1_1") (pintype "passive"))
      (node (ref "T5") (pin "E") (pinfunction "E_E") (pintype "passive"))
    )
    (net (code "65") (name "Net-(U$2-2{slash}PWM)") (class "Default")
      (node (ref "R20") (pin "2") (pinfunction "2_2") (pintype "passive"))
      (node (ref "U$2") (pin "2") (pinfunction "2/PWM_2") (pintype "bidirectional"))
    )
    (net (code "66") (name "Net-(U$2-29{slash}PWM)") (class "Default")
      (node (ref "R21") (pin "2") (pinfunction "2_2") (pintype "passive"))
      (node (ref "U$2") (pin "29") (pinfunction "29/PWM_29") (pintype "bidirectional"))
    )
    (net (code "67") (name "Net-(U$4-C-)") (class "Default")
      (node (ref "R27") (pin "1") (pinfunction "1_1") (pintype "passive"))
      (node (ref "U$4") (pin "K-") (pinfunction "C-_K-") (pintype "passive"))
    )
    (net (code "68") (name "RASPBERRY_RX") (class "Default")
      (node (ref "RASPBERRY_PI") (pin "3") (pinfunction "3_3") (pintype "passive"))
      (node (ref "U$2") (pin "1") (pinfunction "1/TX1/MISO1_1") (pintype "bidirectional"))
    )
    (net (code "69") (name "RASPBERRY_TX") (class "Default")
      (node (ref "RASPBERRY_PI") (pin "4") (pinfunction "4_4") (pintype "passive"))
      (node (ref "U$2") (pin "0") (pinfunction "0/RX1/MOSI1_0") (pintype "bidirectional"))
    )
    (net (code "70") (name "SCL") (class "Default")
      (node (ref "FILET_MOTEURS+BUTEES") (pin "13") (pinfunction "13_13") (pintype "passive"))
      (node (ref "PHARES_AR_D") (pin "5") (pinfunction "5_5") (pintype "passive"))
      (node (ref "PHARES_AR_G") (pin "5") (pinfunction "5_5") (pintype "passive"))
      (node (ref "PHARES_AV_D") (pin "5") (pinfunction "5_5") (pintype "passive"))
      (node (ref "PHARES_AV_G") (pin "5") (pinfunction "5_5") (pintype "passive"))
      (node (ref "TABLEAU_DE_BORD") (pin "5") (pinfunction "5_5") (pintype "passive"))
      (node (ref "TOF_FLAN_AR_D") (pin "4") (pinfunction "4_4") (pintype "passive"))
      (node (ref "TOF_FLAN_AR_G") (pin "4") (pinfunction "4_4") (pintype "passive"))
      (node (ref "TOF_FLAN_AV_D") (pin "4") (pinfunction "4_4") (pintype "passive"))
      (node (ref "TOF_FLAN_AV_G") (pin "4") (pinfunction "4_4") (pintype "passive"))
      (node (ref "U$2") (pin "19/A5") (pinfunction "19/A5/SCL0_19/A5") (pintype "bidirectional"))
    )
    (net (code "71") (name "SDA") (class "Default")
      (node (ref "FILET_MOTEURS+BUTEES") (pin "11") (pinfunction "11_11") (pintype "passive"))
      (node (ref "PHARES_AR_D") (pin "3") (pinfunction "3_3") (pintype "passive"))
      (node (ref "PHARES_AR_G") (pin "3") (pinfunction "3_3") (pintype "passive"))
      (node (ref "PHARES_AV_D") (pin "3") (pinfunction "3_3") (pintype "passive"))
      (node (ref "PHARES_AV_G") (pin "3") (pinfunction "3_3") (pintype "passive"))
      (node (ref "TABLEAU_DE_BORD") (pin "3") (pinfunction "3_3") (pintype "passive"))
      (node (ref "TOF_FLAN_AR_D") (pin "3") (pinfunction "3_3") (pintype "passive"))
      (node (ref "TOF_FLAN_AR_G") (pin "3") (pinfunction "3_3") (pintype "passive"))
      (node (ref "TOF_FLAN_AV_D") (pin "3") (pinfunction "3_3") (pintype "passive"))
      (node (ref "TOF_FLAN_AV_G") (pin "3") (pinfunction "3_3") (pintype "passive"))
      (node (ref "U$2") (pin "18/A4") (pinfunction "18/A4/SDA0_18/A4") (pintype "bidirectional"))
    )
    (net (code "72") (name "STANDBY_12V") (class "Default")
      (node (ref "BOUTON_AR_URG") (pin "1") (pinfunction "KL_1") (pintype "passive"))
      (node (ref "C4") (pin "+") (pinfunction "+_+") (pintype "passive"))
      (node (ref "DC2") (pin "1") (pinfunction "VIN_1") (pintype "passive"))
      (node (ref "U$1") (pin "C") (pinfunction "C-_C") (pintype "passive"))
    )
    (net (code "73") (name "TOF_BACK_EN") (class "Default")
      (node (ref "FILET_MOTEURS+BUTEES") (pin "10") (pinfunction "10_10") (pintype "passive"))
      (node (ref "U$2") (pin "34/A15") (pinfunction "34/A15/RX5_34/A15") (pintype "bidirectional"))
    )
    (net (code "74") (name "TOF_FLAN_AR_D_EN") (class "Default")
      (node (ref "TOF_FLAN_AR_D") (pin "5") (pinfunction "5_5") (pintype "passive"))
      (node (ref "U$2") (pin "31/A12") (pinfunction "31/A12/RX4_31/A12") (pintype "bidirectional"))
    )
    (net (code "75") (name "TOF_FLAN_AR_G_EN") (class "Default")
      (node (ref "TOF_FLAN_AR_G") (pin "5") (pinfunction "5_5") (pintype "passive"))
      (node (ref "U$2") (pin "25") (pinfunction "25_25") (pintype "bidirectional"))
    )
    (net (code "76") (name "TOF_FLAN_AV_D_EN") (class "Default")
      (node (ref "TOF_FLAN_AV_D") (pin "5") (pinfunction "5_5") (pintype "passive"))
      (node (ref "U$2") (pin "32/A13") (pinfunction "32/A13/TX4/SCK1_32/A13") (pintype "bidirectional"))
    )
    (net (code "77") (name "TOF_FLAN_AV_G_EN") (class "Default")
      (node (ref "TOF_FLAN_AV_G") (pin "5") (pinfunction "5_5") (pintype "passive"))
      (node (ref "U$2") (pin "24") (pinfunction "24_24") (pintype "bidirectional"))
    )
    (net (code "78") (name "TOF_FRONT_EN") (class "Default")
      (node (ref "TABLEAU_DE_BORD") (pin "7") (pinfunction "7_7") (pintype "passive"))
      (node (ref "U$2") (pin "27") (pinfunction "27_27") (pintype "bidirectional"))
    )
    (net (code "79") (name "TOF_PHARE_AR_D_EN") (class "Default")
      (node (ref "PHARES_AR_D") (pin "7") (pinfunction "7_7") (pintype "passive"))
      (node (ref "U$2") (pin "33/A14") (pinfunction "33/A14/TX5_33/A14") (pintype "bidirectional"))
    )
    (net (code "80") (name "TOF_PHARE_AR_G_EN") (class "Default")
      (node (ref "PHARES_AR_G") (pin "7") (pinfunction "7_7") (pintype "passive"))
      (node (ref "U$2") (pin "39/A20") (pinfunction "39/A20_39/A20") (pintype "bidirectional"))
    )
    (net (code "81") (name "TOF_PHARE_AV_D_EN") (class "Default")
      (node (ref "PHARES_AV_D") (pin "7") (pinfunction "7_7") (pintype "passive"))
      (node (ref "U$2") (pin "28") (pinfunction "28_28") (pintype "bidirectional"))
    )
    (net (code "82") (name "TOF_PHARE_AV_G_EN") (class "Default")
      (node (ref "PHARES_AV_G") (pin "7") (pinfunction "7_7") (pintype "passive"))
      (node (ref "U$2") (pin "26") (pinfunction "26_26") (pintype "bidirectional"))
    )
    (net (code "83") (name "UART_AX12") (class "Default")
      (node (ref "U$2") (pin "10") (pinfunction "10/TX2/PWM_10") (pintype "bidirectional"))
      (node (ref "U$2") (pin "9") (pinfunction "9/RX2/PWM_9") (pintype "bidirectional"))
      (node (ref "U$3") (pin "TXI-1") (pinfunction "TXI-1_TXI-1") (pintype "bidirectional"))
    )
    (net (code "84") (name "UART_AX12_5V") (class "Default")
      (node (ref "AX12_DIRECTION") (pin "3") (pinfunction "3_3") (pintype "passive"))
      (node (ref "AX12_FILET") (pin "3") (pinfunction "3_3") (pintype "passive"))
      (node (ref "U$3") (pin "TXO-1") (pinfunction "TXO-1_TXO-1") (pintype "bidirectional"))
    )
    (net (code "85") (name "VENTILATEUR_+") (class "Default")
      (node (ref "PONT_H_FILET_1") (pin "3") (pinfunction "OUT2_3") (pintype "output"))
      (node (ref "VENTILATEUR") (pin "1") (pinfunction "1_1") (pintype "passive"))
    )
    (net (code "86") (name "VENTILATEUR_-") (class "Default")
      (node (ref "PONT_H_FILET_1") (pin "2") (pinfunction "OUT1_2") (pintype "output"))
      (node (ref "VENTILATEUR") (pin "2") (pinfunction "2_2") (pintype "passive"))
    )
    (net (code "87") (name "VENTILATEUR_EN") (class "Default")
      (node (ref "PONT_H_FILET_1") (pin "5") (pinfunction "INPUT1_5") (pintype "input"))
      (node (ref "R7") (pin "2") (pinfunction "2_2") (pintype "passive"))
      (node (ref "U$2") (pin "17/A3") (pinfunction "17/A3/PWM_17/A3") (pintype "bidirectional"))
    )
    (net (code "88") (name "unconnected-(FILET_MOTEURS+BUTEES-Pad2)") (class "Default")
      (node (ref "FILET_MOTEURS+BUTEES") (pin "2") (pinfunction "2_2") (pintype "passive"))
    )
    (net (code "89") (name "unconnected-(PHARES_AR_D-Pad9)") (class "Default")
      (node (ref "PHARES_AR_D") (pin "9") (pinfunction "9_9") (pintype "passive"))
    )
    (net (code "90") (name "unconnected-(PHARES_AR_G-Pad9)") (class "Default")
      (node (ref "PHARES_AR_G") (pin "9") (pinfunction "9_9") (pintype "passive"))
    )
    (net (code "91") (name "unconnected-(PHARES_AV_D-Pad8)") (class "Default")
      (node (ref "PHARES_AV_D") (pin "8") (pinfunction "8_8") (pintype "passive"))
    )
    (net (code "92") (name "unconnected-(PHARES_AV_G-Pad8)") (class "Default")
      (node (ref "PHARES_AV_G") (pin "8") (pinfunction "8_8") (pintype "passive"))
    )
    (net (code "93") (name "unconnected-(U$2-PadA26)") (class "Default")
      (node (ref "U$2") (pin "A26") (pinfunction "A26_A26") (pintype "bidirectional"))
    )
    (net (code "94") (name "unconnected-(U$3-PadRXI-1)") (class "Default")
      (node (ref "U$3") (pin "RXI-1") (pinfunction "RXI-1_RXI-1") (pintype "bidirectional"))
    )
    (net (code "95") (name "unconnected-(U$3-PadRXI-2)") (class "Default")
      (node (ref "U$3") (pin "RXI-2") (pinfunction "RXI-2_RXI-2") (pintype "bidirectional"))
    )
    (net (code "96") (name "unconnected-(U$3-PadRXO-1)") (class "Default")
      (node (ref "U$3") (pin "RXO-1") (pinfunction "RXO-1_RXO-1") (pintype "bidirectional"))
    )
    (net (code "97") (name "unconnected-(U$3-PadRXO-2)") (class "Default")
      (node (ref "U$3") (pin "RXO-2") (pinfunction "RXO-2_RXO-2") (pintype "bidirectional"))
    )
    (net (code "98") (name "unconnected-(U$3-PadTXI-2)") (class "Default")
      (node (ref "U$3") (pin "TXI-2") (pinfunction "TXI-2_TXI-2") (pintype "bidirectional"))
    )
    (net (code "99") (name "unconnected-(U$3-PadTXO-2)") (class "Default")
      (node (ref "U$3") (pin "TXO-2") (pinfunction "TXO-2_TXO-2") (pintype "bidirectional"))
    )
  )
)
